# tiny_breadboard_21x21.net
KiCad netlist of a schematic drawn in EAGLE
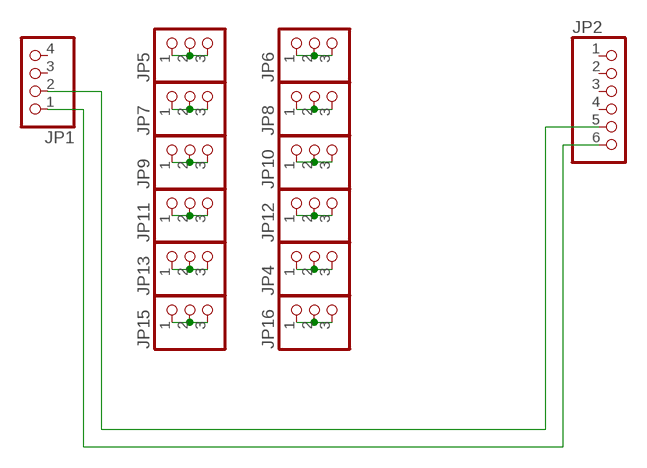
[diagram p0: schematic, sheet 1]

(export (version "E")
  (design (tool "Eeschema 10.0.6"))
  (components
    (comp (ref "JP1")
      (value "PINHD-1X4")
      (footprint "eagle-import:1X04")
      (libsource (lib "eagle-import") (part "PINHD-1X4"))
    )
    (comp (ref "JP2")
      (value "PINHD-1X6")
      (footprint "eagle-import:1X06")
      (libsource (lib "eagle-import") (part "PINHD-1X6"))
    )
    (comp (ref "JP4")
      (value "PINHD-1X3")
      (footprint "eagle-import:1X03")
      (libsource (lib "eagle-import") (part "PINHD-1X3"))
    )
    (comp (ref "JP5")
      (value "PINHD-1X3")
      (footprint "eagle-import:1X03")
      (libsource (lib "eagle-import") (part "PINHD-1X3"))
    )
    (comp (ref "JP6")
      (value "PINHD-1X3")
      (footprint "eagle-import:1X03")
      (libsource (lib "eagle-import") (part "PINHD-1X3"))
    )
    (comp (ref "JP7")
      (value "PINHD-1X3")
      (footprint "eagle-import:1X03")
      (libsource (lib "eagle-import") (part "PINHD-1X3"))
    )
    (comp (ref "JP8")
      (value "PINHD-1X3")
      (footprint "eagle-import:1X03")
      (libsource (lib "eagle-import") (part "PINHD-1X3"))
    )
    (comp (ref "JP9")
      (value "PINHD-1X3")
      (footprint "eagle-import:1X03")
      (libsource (lib "eagle-import") (part "PINHD-1X3"))
    )
    (comp (ref "JP10")
      (value "PINHD-1X3")
      (footprint "eagle-import:1X03")
      (libsource (lib "eagle-import") (part "PINHD-1X3"))
    )
    (comp (ref "JP11")
      (value "PINHD-1X3")
      (footprint "eagle-import:1X03")
      (libsource (lib "eagle-import") (part "PINHD-1X3"))
    )
    (comp (ref "JP12")
      (value "PINHD-1X3")
      (footprint "eagle-import:1X03")
      (libsource (lib "eagle-import") (part "PINHD-1X3"))
    )
    (comp (ref "JP13")
      (value "PINHD-1X3")
      (footprint "eagle-import:1X03")
      (libsource (lib "eagle-import") (part "PINHD-1X3"))
    )
    (comp (ref "JP15")
      (value "PINHD-1X3")
      (footprint "eagle-import:1X03")
      (libsource (lib "eagle-import") (part "PINHD-1X3"))
    )
    (comp (ref "JP16")
      (value "PINHD-1X3")
      (footprint "eagle-import:1X03")
      (libsource (lib "eagle-import") (part "PINHD-1X3"))
    )
  )
  (nets
    (net (code "1") (name "Net-(JP1-Pad1)") (class "Default")
      (node (ref "JP1") (pin "1") (pinfunction "1_1") (pintype "passive"))
      (node (ref "JP2") (pin "6") (pinfunction "6_6") (pintype "passive"))
    )
    (net (code "2") (name "Net-(JP1-Pad2)") (class "Default")
      (node (ref "JP1") (pin "2") (pinfunction "2_2") (pintype "passive"))
      (node (ref "JP2") (pin "5") (pinfunction "5_5") (pintype "passive"))
    )
    (net (code "3") (name "Net-(JP4-Pad1)") (class "Default")
      (node (ref "JP4") (pin "1") (pinfunction "1_1") (pintype "passive"))
      (node (ref "JP4") (pin "2") (pinfunction "2_2") (pintype "passive"))
      (node (ref "JP4") (pin "3") (pinfunction "3_3") (pintype "passive"))
    )
    (net (code "4") (name "Net-(JP5-Pad1)") (class "Default")
      (node (ref "JP5") (pin "1") (pinfunction "1_1") (pintype "passive"))
      (node (ref "JP5") (pin "2") (pinfunction "2_2") (pintype "passive"))
      (node (ref "JP5") (pin "3") (pinfunction "3_3") (pintype "passive"))
    )
    (net (code "5") (name "Net-(JP6-Pad1)") (class "Default")
      (node (ref "JP6") (pin "1") (pinfunction "1_1") (pintype "passive"))
      (node (ref "JP6") (pin "2") (pinfunction "2_2") (pintype "passive"))
      (node (ref "JP6") (pin "3") (pinfunction "3_3") (pintype "passive"))
    )
    (net (code "6") (name "Net-(JP7-Pad1)") (class "Default")
      (node (ref "JP7") (pin "1") (pinfunction "1_1") (pintype "passive"))
      (node (ref "JP7") (pin "2") (pinfunction "2_2") (pintype "passive"))
      (node (ref "JP7") (pin "3") (pinfunction "3_3") (pintype "passive"))
    )
    (net (code "7") (name "Net-(JP8-Pad1)") (class "Default")
      (node (ref "JP8") (pin "1") (pinfunction "1_1") (pintype "passive"))
      (node (ref "JP8") (pin "2") (pinfunction "2_2") (pintype "passive"))
      (node (ref "JP8") (pin "3") (pinfunction "3_3") (pintype "passive"))
    )
    (net (code "8") (name "Net-(JP9-Pad1)") (class "Default")
      (node (ref "JP9") (pin "1") (pinfunction "1_1") (pintype "passive"))
      (node (ref "JP9") (pin "2") (pinfunction "2_2") (pintype "passive"))
      (node (ref "JP9") (pin "3") (pinfunction "3_3") (pintype "passive"))
    )
    (net (code "9") (name "Net-(JP10-Pad1)") (class "Default")
      (node (ref "JP10") (pin "1") (pinfunction "1_1") (pintype "passive"))
      (node (ref "JP10") (pin "2") (pinfunction "2_2") (pintype "passive"))
      (node (ref "JP10") (pin "3") (pinfunction "3_3") (pintype "passive"))
    )
    (net (code "10") (name "Net-(JP11-Pad1)") (class "Default")
      (node (ref "JP11") (pin "1") (pinfunction "1_1") (pintype "passive"))
      (node (ref "JP11") (pin "2") (pinfunction "2_2") (pintype "passive"))
      (node (ref "JP11") (pin "3") (pinfunction "3_3") (pintype "passive"))
    )
    (net (code "11") (name "Net-(JP12-Pad1)") (class "Default")
      (node (ref "JP12") (pin "1") (pinfunction "1_1") (pintype "passive"))
      (node (ref "JP12") (pin "2") (pinfunction "2_2") (pintype "passive"))
      (node (ref "JP12") (pin "3") (pinfunction "3_3") (pintype "passive"))
    )
    (net (code "12") (name "Net-(JP13-Pad1)") (class "Default")
      (node (ref "JP13") (pin "1") (pinfunction "1_1") (pintype "passive"))
      (node (ref "JP13") (pin "2") (pinfunction "2_2") (pintype "passive"))
      (node (ref "JP13") (pin "3") (pinfunction "3_3") (pintype "passive"))
    )
    (net (code "13") (name "Net-(JP15-Pad1)") (class "Default")
      (node (ref "JP15") (pin "1") (pinfunction "1_1") (pintype "passive"))
      (node (ref "JP15") (pin "2") (pinfunction "2_2") (pintype "passive"))
      (node (ref "JP15") (pin "3") (pinfunction "3_3") (pintype "passive"))
    )
    (net (code "14") (name "Net-(JP16-Pad1)") (class "Default")
      (node (ref "JP16") (pin "1") (pinfunction "1_1") (pintype "passive"))
      (node (ref "JP16") (pin "2") (pinfunction "2_2") (pintype "passive"))
      (node (ref "JP16") (pin "3") (pinfunction "3_3") (pintype "passive"))
    )
    (net (code "15") (name "unconnected-(JP1-Pad3)") (class "Default")
      (node (ref "JP1") (pin "3") (pinfunction "3_3") (pintype "passive"))
    )
    (net (code "16") (name "unconnected-(JP1-Pad4)") (class "Default")
      (node (ref "JP1") (pin "4") (pinfunction "4_4") (pintype "passive"))
    )
    (net (code "17") (name "unconnected-(JP2-Pad1)") (class "Default")
      (node (ref "JP2") (pin "1") (pinfunction "1_1") (pintype "passive"))
    )
    (net (code "18") (name "unconnected-(JP2-Pad2)") (class "Default")
      (node (ref "JP2") (pin "2") (pinfunction "2_2") (pintype "passive"))
    )
    (net (code "19") (name "unconnected-(JP2-Pad3)") (class "Default")
      (node (ref "JP2") (pin "3") (pinfunction "3_3") (pintype "passive"))
    )
    (net (code "20") (name "unconnected-(JP2-Pad4)") (class "Default")
      (node (ref "JP2") (pin "4") (pinfunction "4_4") (pintype "passive"))
    )
  )
)
